# COBConnector.net
KiCad netlist of a schematic drawn in Altium Designer
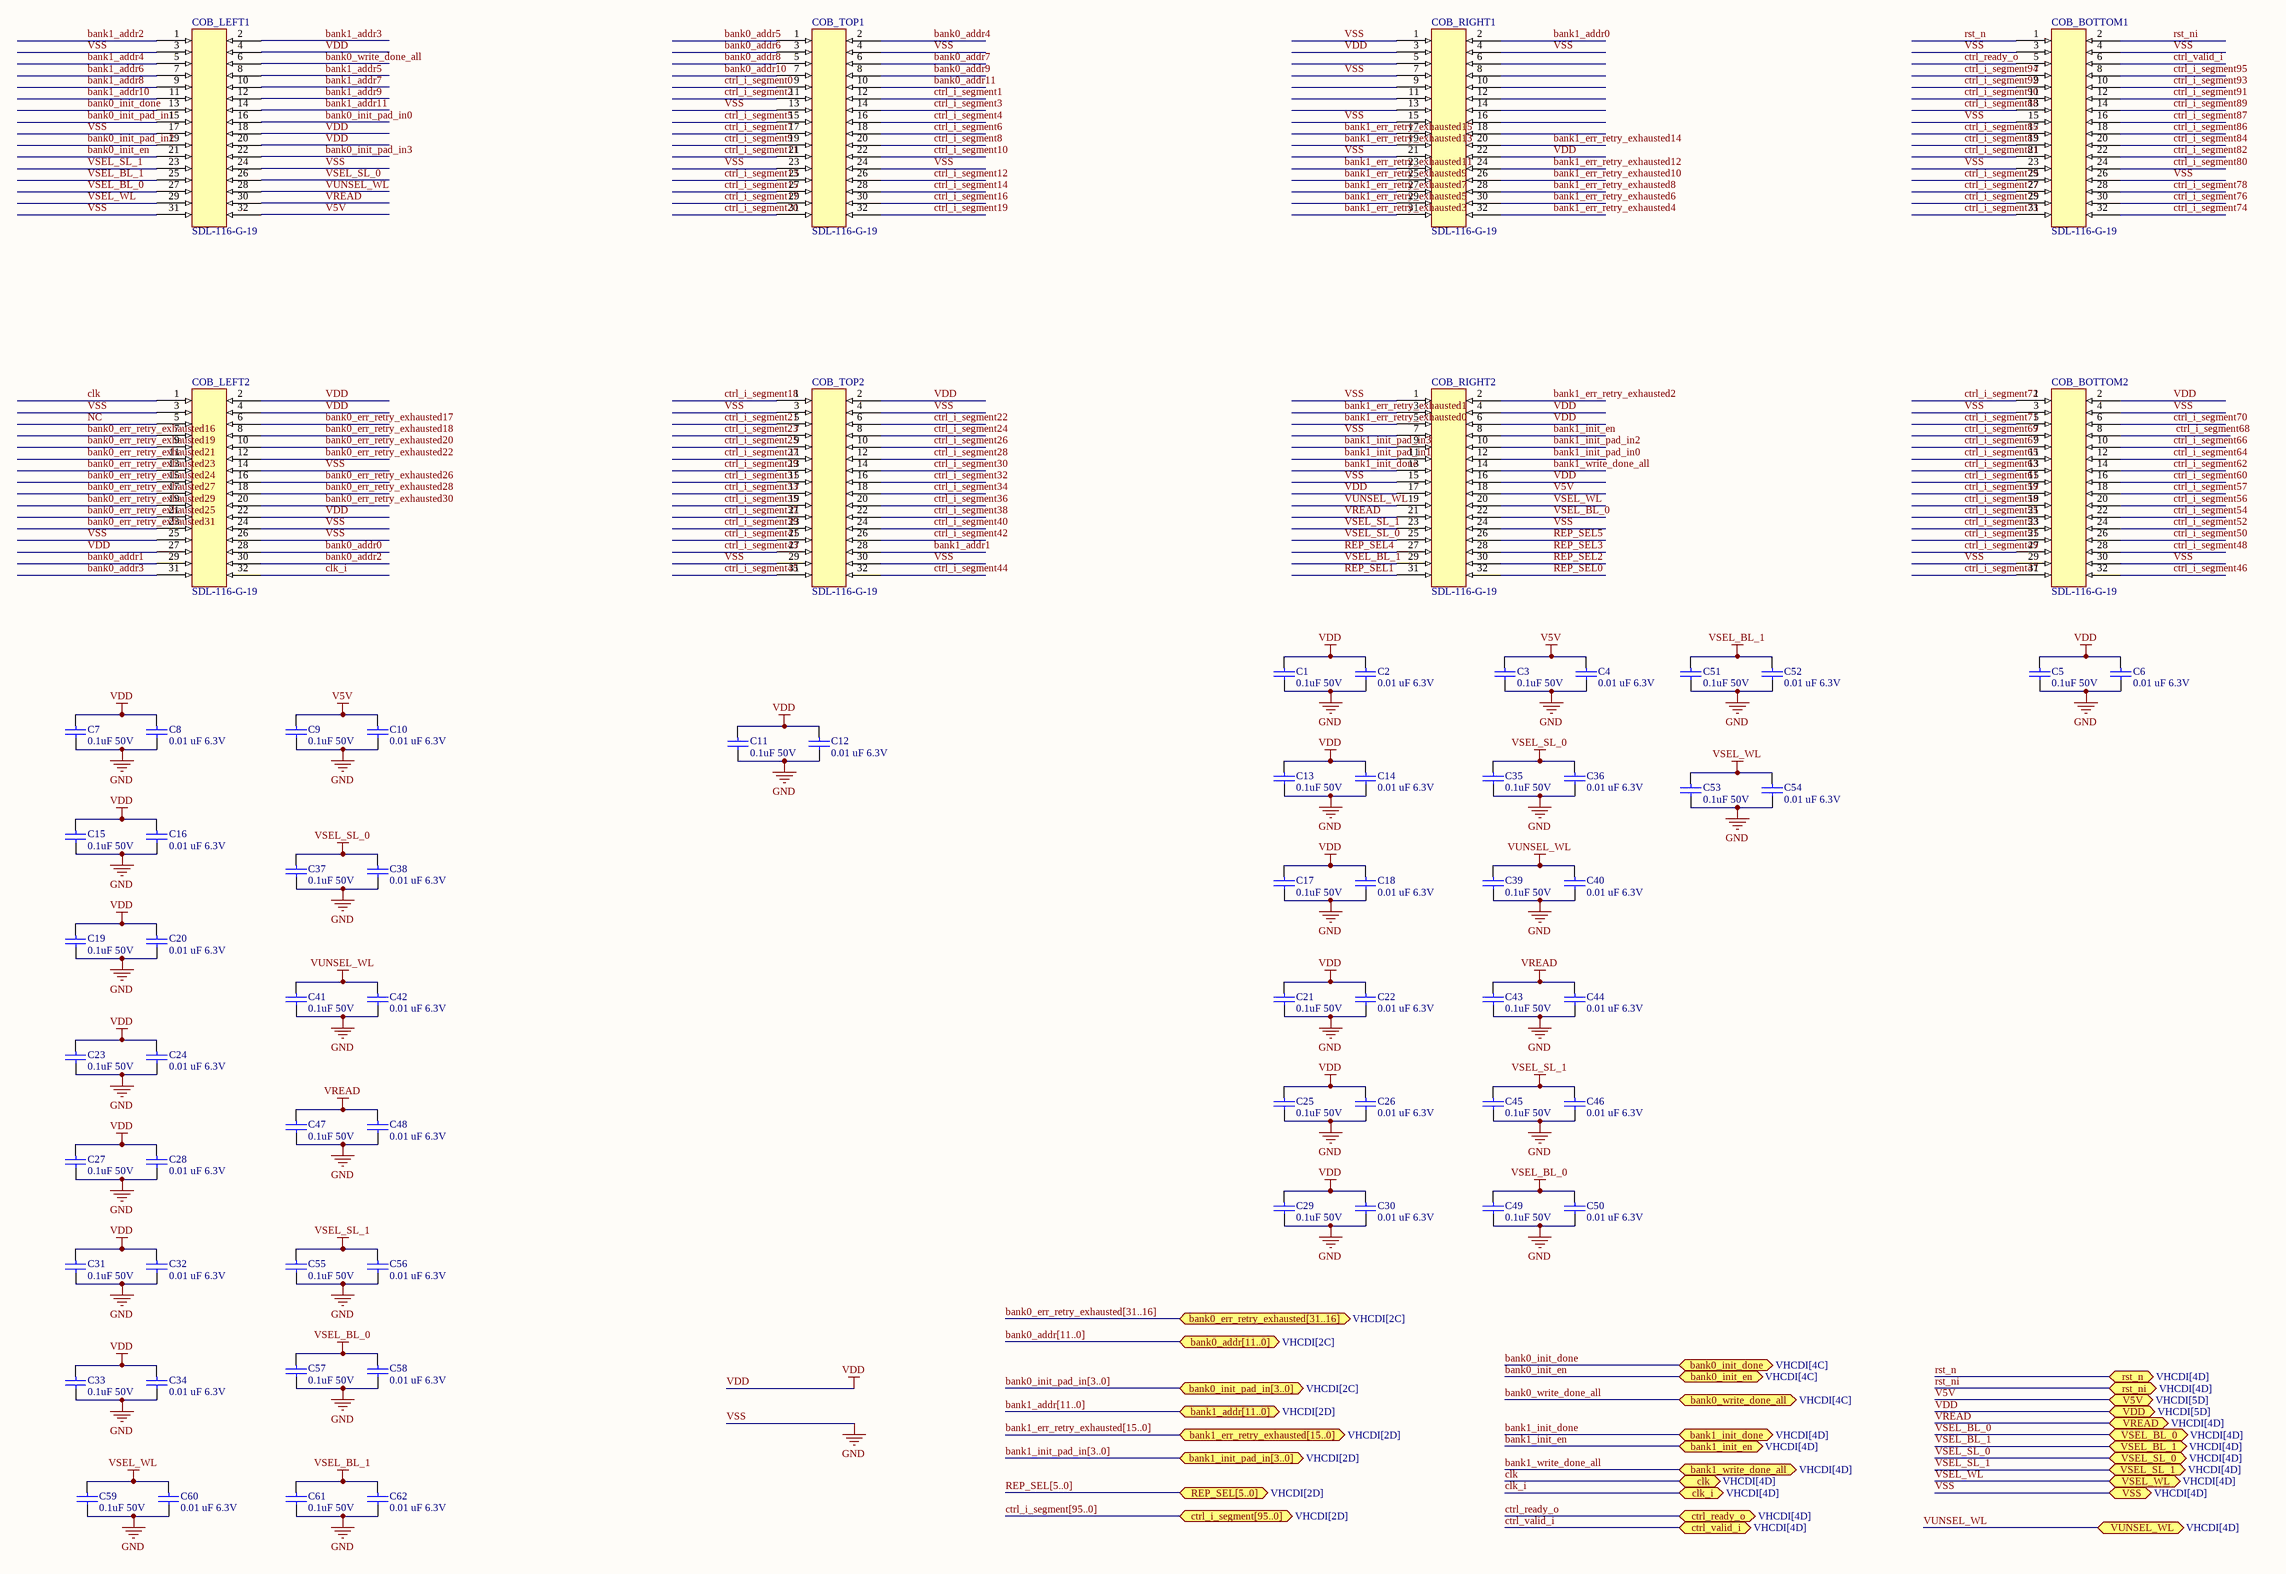
[diagram p0: COBConnector.SchDoc]

(export (version "E")
  (design (tool "Eeschema 10.0.6"))
  (components
    (comp (ref "C1")
      (value "0.1uF 50V")
      (footprint "C0603-XXXXXX-XXX")
      (description "0.1 µF ±20% 50V Ceramic Capacitor X7R 0603")
      (libsource (lib "00-100001-001") (part "C0603C104M5RAC7867"))
    )
    (comp (ref "C2")
      (value "0.01 uF 6.3V")
      (footprint "C0603-XXXXXX-XXX")
      (description "Multilayer Ceramic Capacitors MLCC - SMD/SMT 6.3V 0.01uF X7R 0603 20%")
      (libsource (lib "00-100001-001") (part "C0603F103M9RACTU"))
    )
    (comp (ref "C3")
      (value "0.1uF 50V")
      (footprint "C0603-XXXXXX-XXX")
      (description "0.1 µF ±20% 50V Ceramic Capacitor X7R 0603")
      (libsource (lib "00-100001-001") (part "C0603C104M5RAC7867"))
    )
    (comp (ref "C4")
      (value "0.01 uF 6.3V")
      (footprint "C0603-XXXXXX-XXX")
      (description "Multilayer Ceramic Capacitors MLCC - SMD/SMT 6.3V 0.01uF X7R 0603 20%")
      (libsource (lib "00-100001-001") (part "C0603F103M9RACTU"))
    )
    (comp (ref "C5")
      (value "0.1uF 50V")
      (footprint "C0603-XXXXXX-XXX")
      (description "0.1 µF ±20% 50V Ceramic Capacitor X7R 0603")
      (libsource (lib "00-100001-001") (part "C0603C104M5RAC7867"))
    )
    (comp (ref "C6")
      (value "0.01 uF 6.3V")
      (footprint "C0603-XXXXXX-XXX")
      (description "Multilayer Ceramic Capacitors MLCC - SMD/SMT 6.3V 0.01uF X7R 0603 20%")
      (libsource (lib "00-100001-001") (part "C0603F103M9RACTU"))
    )
    (comp (ref "C7")
      (value "0.1uF 50V")
      (footprint "C0603-XXXXXX-XXX")
      (description "0.1 µF ±20% 50V Ceramic Capacitor X7R 0603")
      (libsource (lib "00-100001-001") (part "C0603C104M5RAC7867"))
    )
    (comp (ref "C8")
      (value "0.01 uF 6.3V")
      (footprint "C0603-XXXXXX-XXX")
      (description "Multilayer Ceramic Capacitors MLCC - SMD/SMT 6.3V 0.01uF X7R 0603 20%")
      (libsource (lib "00-100001-001") (part "C0603F103M9RACTU"))
    )
    (comp (ref "C9")
      (value "0.1uF 50V")
      (footprint "C0603-XXXXXX-XXX")
      (description "0.1 µF ±20% 50V Ceramic Capacitor X7R 0603")
      (libsource (lib "00-100001-001") (part "C0603C104M5RAC7867"))
    )
    (comp (ref "C10")
      (value "0.01 uF 6.3V")
      (footprint "C0603-XXXXXX-XXX")
      (description "Multilayer Ceramic Capacitors MLCC - SMD/SMT 6.3V 0.01uF X7R 0603 20%")
      (libsource (lib "00-100001-001") (part "C0603F103M9RACTU"))
    )
    (comp (ref "C11")
      (value "0.1uF 50V")
      (footprint "C0603-XXXXXX-XXX")
      (description "0.1 µF ±20% 50V Ceramic Capacitor X7R 0603")
      (libsource (lib "00-100001-001") (part "C0603C104M5RAC7867"))
    )
    (comp (ref "C12")
      (value "0.01 uF 6.3V")
      (footprint "C0603-XXXXXX-XXX")
      (description "Multilayer Ceramic Capacitors MLCC - SMD/SMT 6.3V 0.01uF X7R 0603 20%")
      (libsource (lib "00-100001-001") (part "C0603F103M9RACTU"))
    )
    (comp (ref "C13")
      (value "0.1uF 50V")
      (footprint "C0603-XXXXXX-XXX")
      (description "0.1 µF ±20% 50V Ceramic Capacitor X7R 0603")
      (libsource (lib "00-100001-001") (part "C0603C104M5RAC7867"))
    )
    (comp (ref "C14")
      (value "0.01 uF 6.3V")
      (footprint "C0603-XXXXXX-XXX")
      (description "Multilayer Ceramic Capacitors MLCC - SMD/SMT 6.3V 0.01uF X7R 0603 20%")
      (libsource (lib "00-100001-001") (part "C0603F103M9RACTU"))
    )
    (comp (ref "C15")
      (value "0.1uF 50V")
      (footprint "C0603-XXXXXX-XXX")
      (description "0.1 µF ±20% 50V Ceramic Capacitor X7R 0603")
      (libsource (lib "00-100001-001") (part "C0603C104M5RAC7867"))
    )
    (comp (ref "C16")
      (value "0.01 uF 6.3V")
      (footprint "C0603-XXXXXX-XXX")
      (description "Multilayer Ceramic Capacitors MLCC - SMD/SMT 6.3V 0.01uF X7R 0603 20%")
      (libsource (lib "00-100001-001") (part "C0603F103M9RACTU"))
    )
    (comp (ref "C17")
      (value "0.1uF 50V")
      (footprint "C0603-XXXXXX-XXX")
      (description "0.1 µF ±20% 50V Ceramic Capacitor X7R 0603")
      (libsource (lib "00-100001-001") (part "C0603C104M5RAC7867"))
    )
    (comp (ref "C18")
      (value "0.01 uF 6.3V")
      (footprint "C0603-XXXXXX-XXX")
      (description "Multilayer Ceramic Capacitors MLCC - SMD/SMT 6.3V 0.01uF X7R 0603 20%")
      (libsource (lib "00-100001-001") (part "C0603F103M9RACTU"))
    )
    (comp (ref "C19")
      (value "0.1uF 50V")
      (footprint "C0603-XXXXXX-XXX")
      (description "0.1 µF ±20% 50V Ceramic Capacitor X7R 0603")
      (libsource (lib "00-100001-001") (part "C0603C104M5RAC7867"))
    )
    (comp (ref "C20")
      (value "0.01 uF 6.3V")
      (footprint "C0603-XXXXXX-XXX")
      (description "Multilayer Ceramic Capacitors MLCC - SMD/SMT 6.3V 0.01uF X7R 0603 20%")
      (libsource (lib "00-100001-001") (part "C0603F103M9RACTU"))
    )
    (comp (ref "C21")
      (value "0.1uF 50V")
      (footprint "C0603-XXXXXX-XXX")
      (description "0.1 µF ±20% 50V Ceramic Capacitor X7R 0603")
      (libsource (lib "00-100001-001") (part "C0603C104M5RAC7867"))
    )
    (comp (ref "C22")
      (value "0.01 uF 6.3V")
      (footprint "C0603-XXXXXX-XXX")
      (description "Multilayer Ceramic Capacitors MLCC - SMD/SMT 6.3V 0.01uF X7R 0603 20%")
      (libsource (lib "00-100001-001") (part "C0603F103M9RACTU"))
    )
    (comp (ref "C23")
      (value "0.1uF 50V")
      (footprint "C0603-XXXXXX-XXX")
      (description "0.1 µF ±20% 50V Ceramic Capacitor X7R 0603")
      (libsource (lib "00-100001-001") (part "C0603C104M5RAC7867"))
    )
    (comp (ref "C24")
      (value "0.01 uF 6.3V")
      (footprint "C0603-XXXXXX-XXX")
      (description "Multilayer Ceramic Capacitors MLCC - SMD/SMT 6.3V 0.01uF X7R 0603 20%")
      (libsource (lib "00-100001-001") (part "C0603F103M9RACTU"))
    )
    (comp (ref "C25")
      (value "0.1uF 50V")
      (footprint "C0603-XXXXXX-XXX")
      (description "0.1 µF ±20% 50V Ceramic Capacitor X7R 0603")
      (libsource (lib "00-100001-001") (part "C0603C104M5RAC7867"))
    )
    (comp (ref "C26")
      (value "0.01 uF 6.3V")
      (footprint "C0603-XXXXXX-XXX")
      (description "Multilayer Ceramic Capacitors MLCC - SMD/SMT 6.3V 0.01uF X7R 0603 20%")
      (libsource (lib "00-100001-001") (part "C0603F103M9RACTU"))
    )
    (comp (ref "C27")
      (value "0.1uF 50V")
      (footprint "C0603-XXXXXX-XXX")
      (description "0.1 µF ±20% 50V Ceramic Capacitor X7R 0603")
      (libsource (lib "00-100001-001") (part "C0603C104M5RAC7867"))
    )
    (comp (ref "C28")
      (value "0.01 uF 6.3V")
      (footprint "C0603-XXXXXX-XXX")
      (description "Multilayer Ceramic Capacitors MLCC - SMD/SMT 6.3V 0.01uF X7R 0603 20%")
      (libsource (lib "00-100001-001") (part "C0603F103M9RACTU"))
    )
    (comp (ref "C29")
      (value "0.1uF 50V")
      (footprint "C0603-XXXXXX-XXX")
      (description "0.1 µF ±20% 50V Ceramic Capacitor X7R 0603")
      (libsource (lib "00-100001-001") (part "C0603C104M5RAC7867"))
    )
    (comp (ref "C30")
      (value "0.01 uF 6.3V")
      (footprint "C0603-XXXXXX-XXX")
      (description "Multilayer Ceramic Capacitors MLCC - SMD/SMT 6.3V 0.01uF X7R 0603 20%")
      (libsource (lib "00-100001-001") (part "C0603F103M9RACTU"))
    )
    (comp (ref "C31")
      (value "0.1uF 50V")
      (footprint "C0603-XXXXXX-XXX")
      (description "0.1 µF ±20% 50V Ceramic Capacitor X7R 0603")
      (libsource (lib "00-100001-001") (part "C0603C104M5RAC7867"))
    )
    (comp (ref "C32")
      (value "0.01 uF 6.3V")
      (footprint "C0603-XXXXXX-XXX")
      (description "Multilayer Ceramic Capacitors MLCC - SMD/SMT 6.3V 0.01uF X7R 0603 20%")
      (libsource (lib "00-100001-001") (part "C0603F103M9RACTU"))
    )
    (comp (ref "C33")
      (value "0.1uF 50V")
      (footprint "C0603-XXXXXX-XXX")
      (description "0.1 µF ±20% 50V Ceramic Capacitor X7R 0603")
      (libsource (lib "00-100001-001") (part "C0603C104M5RAC7867"))
    )
    (comp (ref "C34")
      (value "0.01 uF 6.3V")
      (footprint "C0603-XXXXXX-XXX")
      (description "Multilayer Ceramic Capacitors MLCC - SMD/SMT 6.3V 0.01uF X7R 0603 20%")
      (libsource (lib "00-100001-001") (part "C0603F103M9RACTU"))
    )
    (comp (ref "C35")
      (value "0.1uF 50V")
      (footprint "C0603-XXXXXX-XXX")
      (description "0.1 µF ±20% 50V Ceramic Capacitor X7R 0603")
      (libsource (lib "00-100001-001") (part "C0603C104M5RAC7867"))
    )
    (comp (ref "C36")
      (value "0.01 uF 6.3V")
      (footprint "C0603-XXXXXX-XXX")
      (description "Multilayer Ceramic Capacitors MLCC - SMD/SMT 6.3V 0.01uF X7R 0603 20%")
      (libsource (lib "00-100001-001") (part "C0603F103M9RACTU"))
    )
    (comp (ref "C37")
      (value "0.1uF 50V")
      (footprint "C0603-XXXXXX-XXX")
      (description "0.1 µF ±20% 50V Ceramic Capacitor X7R 0603")
      (libsource (lib "00-100001-001") (part "C0603C104M5RAC7867"))
    )
    (comp (ref "C38")
      (value "0.01 uF 6.3V")
      (footprint "C0603-XXXXXX-XXX")
      (description "Multilayer Ceramic Capacitors MLCC - SMD/SMT 6.3V 0.01uF X7R 0603 20%")
      (libsource (lib "00-100001-001") (part "C0603F103M9RACTU"))
    )
    (comp (ref "C39")
      (value "0.1uF 50V")
      (footprint "C0603-XXXXXX-XXX")
      (description "0.1 µF ±20% 50V Ceramic Capacitor X7R 0603")
      (libsource (lib "00-100001-001") (part "C0603C104M5RAC7867"))
    )
    (comp (ref "C40")
      (value "0.01 uF 6.3V")
      (footprint "C0603-XXXXXX-XXX")
      (description "Multilayer Ceramic Capacitors MLCC - SMD/SMT 6.3V 0.01uF X7R 0603 20%")
      (libsource (lib "00-100001-001") (part "C0603F103M9RACTU"))
    )
    (comp (ref "C41")
      (value "0.1uF 50V")
      (footprint "C0603-XXXXXX-XXX")
      (description "0.1 µF ±20% 50V Ceramic Capacitor X7R 0603")
      (libsource (lib "00-100001-001") (part "C0603C104M5RAC7867"))
    )
    (comp (ref "C42")
      (value "0.01 uF 6.3V")
      (footprint "C0603-XXXXXX-XXX")
      (description "Multilayer Ceramic Capacitors MLCC - SMD/SMT 6.3V 0.01uF X7R 0603 20%")
      (libsource (lib "00-100001-001") (part "C0603F103M9RACTU"))
    )
    (comp (ref "C43")
      (value "0.1uF 50V")
      (footprint "C0603-XXXXXX-XXX")
      (description "0.1 µF ±20% 50V Ceramic Capacitor X7R 0603")
      (libsource (lib "00-100001-001") (part "C0603C104M5RAC7867"))
    )
    (comp (ref "C44")
      (value "0.01 uF 6.3V")
      (footprint "C0603-XXXXXX-XXX")
      (description "Multilayer Ceramic Capacitors MLCC - SMD/SMT 6.3V 0.01uF X7R 0603 20%")
      (libsource (lib "00-100001-001") (part "C0603F103M9RACTU"))
    )
    (comp (ref "C45")
      (value "0.1uF 50V")
      (footprint "C0603-XXXXXX-XXX")
      (description "0.1 µF ±20% 50V Ceramic Capacitor X7R 0603")
      (libsource (lib "00-100001-001") (part "C0603C104M5RAC7867"))
    )
    (comp (ref "C46")
      (value "0.01 uF 6.3V")
      (footprint "C0603-XXXXXX-XXX")
      (description "Multilayer Ceramic Capacitors MLCC - SMD/SMT 6.3V 0.01uF X7R 0603 20%")
      (libsource (lib "00-100001-001") (part "C0603F103M9RACTU"))
    )
    (comp (ref "C47")
      (value "0.1uF 50V")
      (footprint "C0603-XXXXXX-XXX")
      (description "0.1 µF ±20% 50V Ceramic Capacitor X7R 0603")
      (libsource (lib "00-100001-001") (part "C0603C104M5RAC7867"))
    )
    (comp (ref "C48")
      (value "0.01 uF 6.3V")
      (footprint "C0603-XXXXXX-XXX")
      (description "Multilayer Ceramic Capacitors MLCC - SMD/SMT 6.3V 0.01uF X7R 0603 20%")
      (libsource (lib "00-100001-001") (part "C0603F103M9RACTU"))
    )
    (comp (ref "C49")
      (value "0.1uF 50V")
      (footprint "C0603-XXXXXX-XXX")
      (description "0.1 µF ±20% 50V Ceramic Capacitor X7R 0603")
      (libsource (lib "00-100001-001") (part "C0603C104M5RAC7867"))
    )
    (comp (ref "C50")
      (value "0.01 uF 6.3V")
      (footprint "C0603-XXXXXX-XXX")
      (description "Multilayer Ceramic Capacitors MLCC - SMD/SMT 6.3V 0.01uF X7R 0603 20%")
      (libsource (lib "00-100001-001") (part "C0603F103M9RACTU"))
    )
    (comp (ref "C51")
      (value "0.1uF 50V")
      (footprint "C0603-XXXXXX-XXX")
      (description "0.1 µF ±20% 50V Ceramic Capacitor X7R 0603")
      (libsource (lib "00-100001-001") (part "C0603C104M5RAC7867"))
    )
    (comp (ref "C52")
      (value "0.01 uF 6.3V")
      (footprint "C0603-XXXXXX-XXX")
      (description "Multilayer Ceramic Capacitors MLCC - SMD/SMT 6.3V 0.01uF X7R 0603 20%")
      (libsource (lib "00-100001-001") (part "C0603F103M9RACTU"))
    )
    (comp (ref "C53")
      (value "0.1uF 50V")
      (footprint "C0603-XXXXXX-XXX")
      (description "0.1 µF ±20% 50V Ceramic Capacitor X7R 0603")
      (libsource (lib "00-100001-001") (part "C0603C104M5RAC7867"))
    )
    (comp (ref "C54")
      (value "0.01 uF 6.3V")
      (footprint "C0603-XXXXXX-XXX")
      (description "Multilayer Ceramic Capacitors MLCC - SMD/SMT 6.3V 0.01uF X7R 0603 20%")
      (libsource (lib "00-100001-001") (part "C0603F103M9RACTU"))
    )
    (comp (ref "C55")
      (value "0.1uF 50V")
      (footprint "C0603-XXXXXX-XXX")
      (description "0.1 µF ±20% 50V Ceramic Capacitor X7R 0603")
      (libsource (lib "00-100001-001") (part "C0603C104M5RAC7867"))
    )
    (comp (ref "C56")
      (value "0.01 uF 6.3V")
      (footprint "C0603-XXXXXX-XXX")
      (description "Multilayer Ceramic Capacitors MLCC - SMD/SMT 6.3V 0.01uF X7R 0603 20%")
      (libsource (lib "00-100001-001") (part "C0603F103M9RACTU"))
    )
    (comp (ref "C57")
      (value "0.1uF 50V")
      (footprint "C0603-XXXXXX-XXX")
      (description "0.1 µF ±20% 50V Ceramic Capacitor X7R 0603")
      (libsource (lib "00-100001-001") (part "C0603C104M5RAC7867"))
    )
    (comp (ref "C58")
      (value "0.01 uF 6.3V")
      (footprint "C0603-XXXXXX-XXX")
      (description "Multilayer Ceramic Capacitors MLCC - SMD/SMT 6.3V 0.01uF X7R 0603 20%")
      (libsource (lib "00-100001-001") (part "C0603F103M9RACTU"))
    )
    (comp (ref "C59")
      (value "0.1uF 50V")
      (footprint "C0603-XXXXXX-XXX")
      (description "0.1 µF ±20% 50V Ceramic Capacitor X7R 0603")
      (libsource (lib "00-100001-001") (part "C0603C104M5RAC7867"))
    )
    (comp (ref "C60")
      (value "0.01 uF 6.3V")
      (footprint "C0603-XXXXXX-XXX")
      (description "Multilayer Ceramic Capacitors MLCC - SMD/SMT 6.3V 0.01uF X7R 0603 20%")
      (libsource (lib "00-100001-001") (part "C0603F103M9RACTU"))
    )
    (comp (ref "C61")
      (value "0.1uF 50V")
      (footprint "C0603-XXXXXX-XXX")
      (description "0.1 µF ±20% 50V Ceramic Capacitor X7R 0603")
      (libsource (lib "00-100001-001") (part "C0603C104M5RAC7867"))
    )
    (comp (ref "C62")
      (value "0.01 uF 6.3V")
      (footprint "C0603-XXXXXX-XXX")
      (description "Multilayer Ceramic Capacitors MLCC - SMD/SMT 6.3V 0.01uF X7R 0603 20%")
      (libsource (lib "00-100001-001") (part "C0603F103M9RACTU"))
    )
    (comp (ref "COB_BOTTOM1")
      (value "SDL-116-G-19")
      (footprint "CON32_2X16_TU_DSL_SAI")
      (libsource (lib "00-100001-001") (part "SDL-116-G-19"))
    )
    (comp (ref "COB_BOTTOM2")
      (value "SDL-116-G-19")
      (footprint "CON32_2X16_TU_DSL_SAI")
      (libsource (lib "00-100001-001") (part "SDL-116-G-19"))
    )
    (comp (ref "COB_LEFT1")
      (value "SDL-116-G-19")
      (footprint "CON32_2X16_TU_DSL_SAI")
      (libsource (lib "00-100001-001") (part "SDL-116-G-19"))
    )
    (comp (ref "COB_LEFT2")
      (value "SDL-116-G-19")
      (footprint "CON32_2X16_TU_DSL_SAI")
      (libsource (lib "00-100001-001") (part "SDL-116-G-19"))
    )
    (comp (ref "COB_RIGHT1")
      (value "SDL-116-G-19")
      (footprint "CON32_2X16_TU_DSL_SAI")
      (libsource (lib "00-100001-001") (part "SDL-116-G-19"))
    )
    (comp (ref "COB_RIGHT2")
      (value "SDL-116-G-19")
      (footprint "CON32_2X16_TU_DSL_SAI")
      (libsource (lib "00-100001-001") (part "SDL-116-G-19"))
    )
    (comp (ref "COB_TOP1")
      (value "SDL-116-G-19")
      (footprint "CON32_2X16_TU_DSL_SAI")
      (libsource (lib "00-100001-001") (part "SDL-116-G-19"))
    )
    (comp (ref "COB_TOP2")
      (value "SDL-116-G-19")
      (footprint "CON32_2X16_TU_DSL_SAI")
      (libsource (lib "00-100001-001") (part "SDL-116-G-19"))
    )
  )
  (nets
    (net (code "1") (name "/NC") (class "Default") (node (ref "COB_LEFT2") (pin "5") (pintype "input")))
    (net (code "2") (name "/REP_SEL0") (class "Default")
      (node (ref "COB_RIGHT2") (pin "32") (pintype "input"))
    )
    (net (code "3") (name "/REP_SEL1") (class "Default")
      (node (ref "COB_RIGHT2") (pin "31") (pintype "input"))
    )
    (net (code "4") (name "/REP_SEL2") (class "Default")
      (node (ref "COB_RIGHT2") (pin "30") (pintype "input"))
    )
    (net (code "5") (name "/REP_SEL3") (class "Default")
      (node (ref "COB_RIGHT2") (pin "28") (pintype "input"))
    )
    (net (code "6") (name "/REP_SEL4") (class "Default")
      (node (ref "COB_RIGHT2") (pin "27") (pintype "input"))
    )
    (net (code "7") (name "/REP_SEL5") (class "Default")
      (node (ref "COB_RIGHT2") (pin "26") (pintype "input"))
    )
    (net (code "9") (name "/bank0_addr0") (class "Default")
      (node (ref "COB_LEFT2") (pin "28") (pintype "input"))
    )
    (net (code "10") (name "/bank0_addr1") (class "Default")
      (node (ref "COB_LEFT2") (pin "29") (pintype "input"))
    )
    (net (code "11") (name "/bank0_addr2") (class "Default")
      (node (ref "COB_LEFT2") (pin "30") (pintype "input"))
    )
    (net (code "12") (name "/bank0_addr3") (class "Default")
      (node (ref "COB_LEFT2") (pin "31") (pintype "input"))
    )
    (net (code "13") (name "/bank0_addr4") (class "Default")
      (node (ref "COB_TOP1") (pin "2") (pintype "input"))
    )
    (net (code "14") (name "/bank0_addr5") (class "Default")
      (node (ref "COB_TOP1") (pin "1") (pintype "input"))
    )
    (net (code "15") (name "/bank0_addr6") (class "Default")
      (node (ref "COB_TOP1") (pin "3") (pintype "input"))
    )
    (net (code "16") (name "/bank0_addr7") (class "Default")
      (node (ref "COB_TOP1") (pin "6") (pintype "input"))
    )
    (net (code "17") (name "/bank0_addr8") (class "Default")
      (node (ref "COB_TOP1") (pin "5") (pintype "input"))
    )
    (net (code "18") (name "/bank0_addr9") (class "Default")
      (node (ref "COB_TOP1") (pin "8") (pintype "input"))
    )
    (net (code "19") (name "/bank0_addr10") (class "Default")
      (node (ref "COB_TOP1") (pin "7") (pintype "input"))
    )
    (net (code "20") (name "/bank0_addr11") (class "Default")
      (node (ref "COB_TOP1") (pin "10") (pintype "input"))
    )
    (net (code "22") (name "/bank0_err_retry_exhausted16") (class "Default")
      (node (ref "COB_LEFT2") (pin "7") (pintype "input"))
    )
    (net (code "23") (name "/bank0_err_retry_exhausted17") (class "Default")
      (node (ref "COB_LEFT2") (pin "6") (pintype "input"))
    )
    (net (code "24") (name "/bank0_err_retry_exhausted18") (class "Default")
      (node (ref "COB_LEFT2") (pin "8") (pintype "input"))
    )
    (net (code "25") (name "/bank0_err_retry_exhausted19") (class "Default")
      (node (ref "COB_LEFT2") (pin "9") (pintype "input"))
    )
    (net (code "26") (name "/bank0_err_retry_exhausted20") (class "Default")
      (node (ref "COB_LEFT2") (pin "10") (pintype "input"))
    )
    (net (code "27") (name "/bank0_err_retry_exhausted21") (class "Default")
      (node (ref "COB_LEFT2") (pin "11") (pintype "input"))
    )
    (net (code "28") (name "/bank0_err_retry_exhausted22") (class "Default")
      (node (ref "COB_LEFT2") (pin "12") (pintype "input"))
    )
    (net (code "29") (name "/bank0_err_retry_exhausted23") (class "Default")
      (node (ref "COB_LEFT2") (pin "13") (pintype "input"))
    )
    (net (code "30") (name "/bank0_err_retry_exhausted24") (class "Default")
      (node (ref "COB_LEFT2") (pin "15") (pintype "input"))
    )
    (net (code "31") (name "/bank0_err_retry_exhausted25") (class "Default")
      (node (ref "COB_LEFT2") (pin "21") (pintype "input"))
    )
    (net (code "32") (name "/bank0_err_retry_exhausted26") (class "Default")
      (node (ref "COB_LEFT2") (pin "16") (pintype "input"))
    )
    (net (code "33") (name "/bank0_err_retry_exhausted27") (class "Default")
      (node (ref "COB_LEFT2") (pin "17") (pintype "input"))
    )
    (net (code "34") (name "/bank0_err_retry_exhausted28") (class "Default")
      (node (ref "COB_LEFT2") (pin "18") (pintype "input"))
    )
    (net (code "35") (name "/bank0_err_retry_exhausted29") (class "Default")
      (node (ref "COB_LEFT2") (pin "19") (pintype "input"))
    )
    (net (code "36") (name "/bank0_err_retry_exhausted30") (class "Default")
      (node (ref "COB_LEFT2") (pin "20") (pintype "input"))
    )
    (net (code "37") (name "/bank0_err_retry_exhausted31") (class "Default")
      (node (ref "COB_LEFT2") (pin "23") (pintype "input"))
    )
    (net (code "39") (name "/bank0_init_done") (class "Default")
      (node (ref "COB_LEFT1") (pin "13") (pintype "input"))
    )
    (net (code "40") (name "/bank0_init_en") (class "Default")
      (node (ref "COB_LEFT1") (pin "21") (pintype "input"))
    )
    (net (code "41") (name "/bank0_init_pad_in0") (class "Default")
      (node (ref "COB_LEFT1") (pin "16") (pintype "input"))
    )
    (net (code "42") (name "/bank0_init_pad_in1") (class "Default")
      (node (ref "COB_LEFT1") (pin "15") (pintype "input"))
    )
    (net (code "43") (name "/bank0_init_pad_in2") (class "Default")
      (node (ref "COB_LEFT1") (pin "19") (pintype "input"))
    )
    (net (code "44") (name "/bank0_init_pad_in3") (class "Default")
      (node (ref "COB_LEFT1") (pin "22") (pintype "input"))
    )
    (net (code "46") (name "/bank0_write_done_all") (class "Default")
      (node (ref "COB_LEFT1") (pin "6") (pintype "input"))
    )
    (net (code "47") (name "/bank1_addr0") (class "Default")
      (node (ref "COB_RIGHT1") (pin "2") (pintype "input"))
    )
    (net (code "48") (name "/bank1_addr1") (class "Default")
      (node (ref "COB_TOP2") (pin "28") (pintype "input"))
    )
    (net (code "49") (name "/bank1_addr2") (class "Default")
      (node (ref "COB_LEFT1") (pin "1") (pintype "input"))
    )
    (net (code "50") (name "/bank1_addr3") (class "Default")
      (node (ref "COB_LEFT1") (pin "2") (pintype "input"))
    )
    (net (code "51") (name "/bank1_addr4") (class "Default")
      (node (ref "COB_LEFT1") (pin "5") (pintype "input"))
    )
    (net (code "52") (name "/bank1_addr5") (class "Default")
      (node (ref "COB_LEFT1") (pin "8") (pintype "input"))
    )
    (net (code "53") (name "/bank1_addr6") (class "Default")
      (node (ref "COB_LEFT1") (pin "7") (pintype "input"))
    )
    (net (code "54") (name "/bank1_addr7") (class "Default")
      (node (ref "COB_LEFT1") (pin "10") (pintype "input"))
    )
    (net (code "55") (name "/bank1_addr8") (class "Default")
      (node (ref "COB_LEFT1") (pin "9") (pintype "input"))
    )
    (net (code "56") (name "/bank1_addr9") (class "Default")
      (node (ref "COB_LEFT1") (pin "12") (pintype "input"))
    )
    (net (code "57") (name "/bank1_addr10") (class "Default")
      (node (ref "COB_LEFT1") (pin "11") (pintype "input"))
    )
    (net (code "58") (name "/bank1_addr11") (class "Default")
      (node (ref "COB_LEFT1") (pin "14") (pintype "input"))
    )
    (net (code "60") (name "/bank1_err_retry_exhausted0") (class "Default")
      (node (ref "COB_RIGHT2") (pin "5") (pintype "input"))
    )
    (net (code "61") (name "/bank1_err_retry_exhausted1") (class "Default")
      (node (ref "COB_RIGHT2") (pin "3") (pintype "input"))
    )
    (net (code "62") (name "/bank1_err_retry_exhausted2") (class "Default")
      (node (ref "COB_RIGHT2") (pin "2") (pintype "input"))
    )
    (net (code "63") (name "/bank1_err_retry_exhausted3") (class "Default")
      (node (ref "COB_RIGHT1") (pin "31") (pintype "input"))
    )
    (net (code "64") (name "/bank1_err_retry_exhausted4") (class "Default")
      (node (ref "COB_RIGHT1") (pin "32") (pintype "input"))
    )
    (net (code "65") (name "/bank1_err_retry_exhausted5") (class "Default")
      (node (ref "COB_RIGHT1") (pin "29") (pintype "input"))
    )
    (net (code "66") (name "/bank1_err_retry_exhausted6") (class "Default")
      (node (ref "COB_RIGHT1") (pin "30") (pintype "input"))
    )
    (net (code "67") (name "/bank1_err_retry_exhausted7") (class "Default")
      (node (ref "COB_RIGHT1") (pin "27") (pintype "input"))
    )
    (net (code "68") (name "/bank1_err_retry_exhausted8") (class "Default")
      (node (ref "COB_RIGHT1") (pin "28") (pintype "input"))
    )
    (net (code "69") (name "/bank1_err_retry_exhausted9") (class "Default")
      (node (ref "COB_RIGHT1") (pin "25") (pintype "input"))
    )
    (net (code "70") (name "/bank1_err_retry_exhausted10") (class "Default")
      (node (ref "COB_RIGHT1") (pin "26") (pintype "input"))
    )
    (net (code "71") (name "/bank1_err_retry_exhausted11") (class "Default")
      (node (ref "COB_RIGHT1") (pin "23") (pintype "input"))
    )
    (net (code "72") (name "/bank1_err_retry_exhausted12") (class "Default")
      (node (ref "COB_RIGHT1") (pin "24") (pintype "input"))
    )
    (net (code "73") (name "/bank1_err_retry_exhausted13") (class "Default")
      (node (ref "COB_RIGHT1") (pin "19") (pintype "input"))
    )
    (net (code "74") (name "/bank1_err_retry_exhausted14") (class "Default")
      (node (ref "COB_RIGHT1") (pin "20") (pintype "input"))
    )
    (net (code "75") (name "/bank1_err_retry_exhausted15") (class "Default")
      (node (ref "COB_RIGHT1") (pin "17") (pintype "input"))
    )
    (net (code "77") (name "/bank1_init_done") (class "Default")
      (node (ref "COB_RIGHT2") (pin "13") (pintype "input"))
    )
    (net (code "78") (name "/bank1_init_en") (class "Default")
      (node (ref "COB_RIGHT2") (pin "8") (pintype "input"))
    )
    (net (code "79") (name "/bank1_init_pad_in0") (class "Default")
      (node (ref "COB_RIGHT2") (pin "12") (pintype "input"))
    )
    (net (code "80") (name "/bank1_init_pad_in1") (class "Default")
      (node (ref "COB_RIGHT2") (pin "11") (pintype "input"))
    )
    (net (code "81") (name "/bank1_init_pad_in2") (class "Default")
      (node (ref "COB_RIGHT2") (pin "10") (pintype "input"))
    )
    (net (code "82") (name "/bank1_init_pad_in3") (class "Default")
      (node (ref "COB_RIGHT2") (pin "9") (pintype "input"))
    )
    (net (code "84") (name "/bank1_write_done_all") (class "Default")
      (node (ref "COB_RIGHT2") (pin "14") (pintype "input"))
    )
    (net (code "85") (name "/clk") (class "Default") (node (ref "COB_LEFT2") (pin "1") (pintype "input")))
    (net (code "86") (name "/clk_i") (class "Default") (node (ref "COB_LEFT2") (pin "32") (pintype "input")))
    (net (code "87") (name "/ctrl_i_segment0") (class "Default")
      (node (ref "COB_TOP1") (pin "9") (pintype "input"))
    )
    (net (code "88") (name "/ctrl_i_segment1") (class "Default")
      (node (ref "COB_TOP1") (pin "12") (pintype "input"))
    )
    (net (code "89") (name "/ctrl_i_segment2") (class "Default")
      (node (ref "COB_TOP1") (pin "11") (pintype "input"))
    )
    (net (code "90") (name "/ctrl_i_segment3") (class "Default")
      (node (ref "COB_TOP1") (pin "14") (pintype "input"))
    )
    (net (code "91") (name "/ctrl_i_segment4") (class "Default")
      (node (ref "COB_TOP1") (pin "16") (pintype "input"))
    )
    (net (code "92") (name "/ctrl_i_segment5") (class "Default")
      (node (ref "COB_TOP1") (pin "15") (pintype "input"))
    )
    (net (code "93") (name "/ctrl_i_segment6") (class "Default")
      (node (ref "COB_TOP1") (pin "18") (pintype "input"))
    )
    (net (code "94") (name "/ctrl_i_segment7") (class "Default")
      (node (ref "COB_TOP1") (pin "17") (pintype "input"))
    )
    (net (code "95") (name "/ctrl_i_segment8") (class "Default")
      (node (ref "COB_TOP1") (pin "20") (pintype "input"))
    )
    (net (code "96") (name "/ctrl_i_segment9") (class "Default")
      (node (ref "COB_TOP1") (pin "19") (pintype "input"))
    )
    (net (code "97") (name "/ctrl_i_segment10") (class "Default")
      (node (ref "COB_TOP1") (pin "22") (pintype "input"))
    )
    (net (code "98") (name "/ctrl_i_segment11") (class "Default")
      (node (ref "COB_TOP1") (pin "21") (pintype "input"))
    )
    (net (code "99") (name "/ctrl_i_segment12") (class "Default")
      (node (ref "COB_TOP1") (pin "26") (pintype "input"))
    )
    (net (code "100") (name "/ctrl_i_segment13") (class "Default")
      (node (ref "COB_TOP1") (pin "25") (pintype "input"))
    )
    (net (code "101") (name "/ctrl_i_segment14") (class "Default")
      (node (ref "COB_TOP1") (pin "28") (pintype "input"))
    )
    (net (code "102") (name "/ctrl_i_segment15") (class "Default")
      (node (ref "COB_TOP1") (pin "27") (pintype "input"))
    )
    (net (code "103") (name "/ctrl_i_segment16") (class "Default")
      (node (ref "COB_TOP1") (pin "30") (pintype "input"))
    )
    (net (code "104") (name "/ctrl_i_segment17") (class "Default")
      (node (ref "COB_TOP1") (pin "29") (pintype "input"))
    )
    (net (code "105") (name "/ctrl_i_segment18") (class "Default")
      (node (ref "COB_TOP2") (pin "1") (pintype "input"))
    )
    (net (code "106") (name "/ctrl_i_segment19") (class "Default")
      (node (ref "COB_TOP1") (pin "32") (pintype "input"))
    )
    (net (code "107") (name "/ctrl_i_segment20") (class "Default")
      (node (ref "COB_TOP1") (pin "31") (pintype "input"))
    )
    (net (code "108") (name "/ctrl_i_segment21") (class "Default")
      (node (ref "COB_TOP2") (pin "5") (pintype "input"))
    )
    (net (code "109") (name "/ctrl_i_segment22") (class "Default")
      (node (ref "COB_TOP2") (pin "6") (pintype "input"))
    )
    (net (code "110") (name "/ctrl_i_segment23") (class "Default")
      (node (ref "COB_TOP2") (pin "7") (pintype "input"))
    )
    (net (code "111") (name "/ctrl_i_segment24") (class "Default")
      (node (ref "COB_TOP2") (pin "8") (pintype "input"))
    )
    (net (code "112") (name "/ctrl_i_segment25") (class "Default")
      (node (ref "COB_TOP2") (pin "9") (pintype "input"))
    )
    (net (code "113") (name "/ctrl_i_segment26") (class "Default")
      (node (ref "COB_TOP2") (pin "10") (pintype "input"))
    )
    (net (code "114") (name "/ctrl_i_segment27") (class "Default")
      (node (ref "COB_TOP2") (pin "11") (pintype "input"))
    )
    (net (code "115") (name "/ctrl_i_segment28") (class "Default")
      (node (ref "COB_TOP2") (pin "12") (pintype "input"))
    )
    (net (code "116") (name "/ctrl_i_segment29") (class "Default")
      (node (ref "COB_TOP2") (pin "13") (pintype "input"))
    )
    (net (code "117") (name "/ctrl_i_segment30") (class "Default")
      (node (ref "COB_TOP2") (pin "14") (pintype "input"))
    )
    (net (code "118") (name "/ctrl_i_segment31") (class "Default")
      (node (ref "COB_TOP2") (pin "15") (pintype "input"))
    )
    (net (code "119") (name "/ctrl_i_segment32") (class "Default")
      (node (ref "COB_TOP2") (pin "16") (pintype "input"))
    )
    (net (code "120") (name "/ctrl_i_segment33") (class "Default")
      (node (ref "COB_TOP2") (pin "17") (pintype "input"))
    )
    (net (code "121") (name "/ctrl_i_segment34") (class "Default")
      (node (ref "COB_TOP2") (pin "18") (pintype "input"))
    )
    (net (code "122") (name "/ctrl_i_segment35") (class "Default")
      (node (ref "COB_TOP2") (pin "19") (pintype "input"))
    )
    (net (code "123") (name "/ctrl_i_segment36") (class "Default")
      (node (ref "COB_TOP2") (pin "20") (pintype "input"))
    )
    (net (code "124") (name "/ctrl_i_segment37") (class "Default")
      (node (ref "COB_TOP2") (pin "21") (pintype "input"))
    )
    (net (code "125") (name "/ctrl_i_segment38") (class "Default")
      (node (ref "COB_TOP2") (pin "22") (pintype "input"))
    )
    (net (code "126") (name "/ctrl_i_segment39") (class "Default")
      (node (ref "COB_TOP2") (pin "23") (pintype "input"))
    )
    (net (code "127") (name "/ctrl_i_segment40") (class "Default")
      (node (ref "COB_TOP2") (pin "24") (pintype "input"))
    )
    (net (code "128") (name "/ctrl_i_segment41") (class "Default")
      (node (ref "COB_TOP2") (pin "25") (pintype "input"))
    )
    (net (code "129") (name "/ctrl_i_segment42") (class "Default")
      (node (ref "COB_TOP2") (pin "26") (pintype "input"))
    )
    (net (code "130") (name "/ctrl_i_segment43") (class "Default")
      (node (ref "COB_TOP2") (pin "27") (pintype "input"))
    )
    (net (code "131") (name "/ctrl_i_segment44") (class "Default")
      (node (ref "COB_TOP2") (pin "32") (pintype "input"))
    )
    (net (code "132") (name "/ctrl_i_segment45") (class "Default")
      (node (ref "COB_TOP2") (pin "31") (pintype "input"))
    )
    (net (code "133") (name "/ctrl_i_segment46") (class "Default")
      (node (ref "COB_BOTTOM2") (pin "32") (pintype "input"))
    )
    (net (code "134") (name "/ctrl_i_segment47") (class "Default")
      (node (ref "COB_BOTTOM2") (pin "31") (pintype "input"))
    )
    (net (code "135") (name "/ctrl_i_segment48") (class "Default")
      (node (ref "COB_BOTTOM2") (pin "28") (pintype "input"))
    )
    (net (code "136") (name "/ctrl_i_segment49") (class "Default")
      (node (ref "COB_BOTTOM2") (pin "27") (pintype "input"))
    )
    (net (code "137") (name "/ctrl_i_segment50") (class "Default")
      (node (ref "COB_BOTTOM2") (pin "26") (pintype "input"))
    )
    (net (code "138") (name "/ctrl_i_segment51") (class "Default")
      (node (ref "COB_BOTTOM2") (pin "25") (pintype "input"))
    )
    (net (code "139") (name "/ctrl_i_segment52") (class "Default")
      (node (ref "COB_BOTTOM2") (pin "24") (pintype "input"))
    )
    (net (code "140") (name "/ctrl_i_segment53") (class "Default")
      (node (ref "COB_BOTTOM2") (pin "23") (pintype "input"))
    )
    (net (code "141") (name "/ctrl_i_segment54") (class "Default")
      (node (ref "COB_BOTTOM2") (pin "22") (pintype "input"))
    )
    (net (code "142") (name "/ctrl_i_segment55") (class "Default")
      (node (ref "COB_BOTTOM2") (pin "21") (pintype "input"))
    )
    (net (code "143") (name "/ctrl_i_segment56") (class "Default")
      (node (ref "COB_BOTTOM2") (pin "20") (pintype "input"))
    )
    (net (code "144") (name "/ctrl_i_segment57") (class "Default")
      (node (ref "COB_BOTTOM2") (pin "18") (pintype "input"))
    )
    (net (code "145") (name "/ctrl_i_segment58") (class "Default")
      (node (ref "COB_BOTTOM2") (pin "19") (pintype "input"))
    )
    (net (code "146") (name "/ctrl_i_segment59") (class "Default")
      (node (ref "COB_BOTTOM2") (pin "17") (pintype "input"))
    )
    (net (code "147") (name "/ctrl_i_segment60") (class "Default")
      (node (ref "COB_BOTTOM2") (pin "16") (pintype "input"))
    )
    (net (code "148") (name "/ctrl_i_segment61") (class "Default")
      (node (ref "COB_BOTTOM2") (pin "15") (pintype "input"))
    )
    (net (code "149") (name "/ctrl_i_segment62") (class "Default")
      (node (ref "COB_BOTTOM2") (pin "14") (pintype "input"))
    )
    (net (code "150") (name "/ctrl_i_segment63") (class "Default")
      (node (ref "COB_BOTTOM2") (pin "13") (pintype "input"))
    )
    (net (code "151") (name "/ctrl_i_segment64") (class "Default")
      (node (ref "COB_BOTTOM2") (pin "12") (pintype "input"))
    )
    (net (code "152") (name "/ctrl_i_segment65") (class "Default")
      (node (ref "COB_BOTTOM2") (pin "11") (pintype "input"))
    )
    (net (code "153") (name "/ctrl_i_segment66") (class "Default")
      (node (ref "COB_BOTTOM2") (pin "10") (pintype "input"))
    )
    (net (code "154") (name "/ctrl_i_segment67") (class "Default")
      (node (ref "COB_BOTTOM2") (pin "9") (pintype "input"))
    )
    (net (code "155") (name "/ctrl_i_segment68") (class "Default")
      (node (ref "COB_BOTTOM2") (pin "8") (pintype "input"))
    )
    (net (code "156") (name "/ctrl_i_segment69") (class "Default")
      (node (ref "COB_BOTTOM2") (pin "7") (pintype "input"))
    )
    (net (code "157") (name "/ctrl_i_segment70") (class "Default")
      (node (ref "COB_BOTTOM2") (pin "6") (pintype "input"))
    )
    (net (code "158") (name "/ctrl_i_segment71") (class "Default")
      (node (ref "COB_BOTTOM2") (pin "5") (pintype "input"))
    )
    (net (code "159") (name "/ctrl_i_segment72") (class "Default")
      (node (ref "COB_BOTTOM2") (pin "1") (pintype "input"))
    )
    (net (code "160") (name "/ctrl_i_segment73") (class "Default")
      (node (ref "COB_BOTTOM1") (pin "31") (pintype "input"))
    )
    (net (code "161") (name "/ctrl_i_segment74") (class "Default")
      (node (ref "COB_BOTTOM1") (pin "32") (pintype "input"))
    )
    (net (code "162") (name "/ctrl_i_segment75") (class "Default")
      (node (ref "COB_BOTTOM1") (pin "29") (pintype "input"))
    )
    (net (code "163") (name "/ctrl_i_segment76") (class "Default")
      (node (ref "COB_BOTTOM1") (pin "30") (pintype "input"))
    )
    (net (code "164") (name "/ctrl_i_segment77") (class "Default")
      (node (ref "COB_BOTTOM1") (pin "27") (pintype "input"))
    )
    (net (code "165") (name "/ctrl_i_segment78") (class "Default")
      (node (ref "COB_BOTTOM1") (pin "28") (pintype "input"))
    )
    (net (code "166") (name "/ctrl_i_segment79") (class "Default")
      (node (ref "COB_BOTTOM1") (pin "25") (pintype "input"))
    )
    (net (code "167") (name "/ctrl_i_segment80") (class "Default")
      (node (ref "COB_BOTTOM1") (pin "24") (pintype "input"))
    )
    (net (code "168") (name "/ctrl_i_segment81") (class "Default")
      (node (ref "COB_BOTTOM1") (pin "21") (pintype "input"))
    )
    (net (code "169") (name "/ctrl_i_segment82") (class "Default")
      (node (ref "COB_BOTTOM1") (pin "22") (pintype "input"))
    )
    (net (code "170") (name "/ctrl_i_segment83") (class "Default")
      (node (ref "COB_BOTTOM1") (pin "19") (pintype "input"))
    )
    (net (code "171") (name "/ctrl_i_segment84") (class "Default")
      (node (ref "COB_BOTTOM1") (pin "20") (pintype "input"))
    )
    (net (code "172") (name "/ctrl_i_segment85") (class "Default")
      (node (ref "COB_BOTTOM1") (pin "17") (pintype "input"))
    )
    (net (code "173") (name "/ctrl_i_segment86") (class "Default")
      (node (ref "COB_BOTTOM1") (pin "18") (pintype "input"))
    )
    (net (code "174") (name "/ctrl_i_segment87") (class "Default")
      (node (ref "COB_BOTTOM1") (pin "16") (pintype "input"))
    )
    (net (code "175") (name "/ctrl_i_segment88") (class "Default")
      (node (ref "COB_BOTTOM1") (pin "13") (pintype "input"))
    )
    (net (code "176") (name "/ctrl_i_segment89") (class "Default")
      (node (ref "COB_BOTTOM1") (pin "14") (pintype "input"))
    )
    (net (code "177") (name "/ctrl_i_segment90") (class "Default")
      (node (ref "COB_BOTTOM1") (pin "11") (pintype "input"))
    )
    (net (code "178") (name "/ctrl_i_segment91") (class "Default")
      (node (ref "COB_BOTTOM1") (pin "12") (pintype "input"))
    )
    (net (code "179") (name "/ctrl_i_segment92") (class "Default")
      (node (ref "COB_BOTTOM1") (pin "9") (pintype "input"))
    )
    (net (code "180") (name "/ctrl_i_segment93") (class "Default")
      (node (ref "COB_BOTTOM1") (pin "10") (pintype "input"))
    )
    (net (code "181") (name "/ctrl_i_segment94") (class "Default")
      (node (ref "COB_BOTTOM1") (pin "7") (pintype "input"))
    )
    (net (code "182") (name "/ctrl_i_segment95") (class "Default")
      (node (ref "COB_BOTTOM1") (pin "8") (pintype "input"))
    )
    (net (code "184") (name "/ctrl_ready_o") (class "Default")
      (node (ref "COB_BOTTOM1") (pin "5") (pintype "input"))
    )
    (net (code "185") (name "/ctrl_valid_i") (class "Default")
      (node (ref "COB_BOTTOM1") (pin "6") (pintype "input"))
    )
    (net (code "186") (name "/rst_n") (class "Default")
      (node (ref "COB_BOTTOM1") (pin "1") (pintype "input"))
    )
    (net (code "187") (name "/rst_ni") (class "Default")
      (node (ref "COB_BOTTOM1") (pin "2") (pintype "input"))
    )
    (net (code "188") (name "GND") (class "Default")
      (node (ref "C1") (pin "2") (pinfunction "2_2") (pintype "passive"))
      (node (ref "C10") (pin "2") (pinfunction "2_2") (pintype "passive"))
      (node (ref "C11") (pin "2") (pinfunction "2_2") (pintype "passive"))
      (node (ref "C12") (pin "2") (pinfunction "2_2") (pintype "passive"))
      (node (ref "C13") (pin "2") (pinfunction "2_2") (pintype "passive"))
      (node (ref "C14") (pin "2") (pinfunction "2_2") (pintype "passive"))
      (node (ref "C15") (pin "2") (pinfunction "2_2") (pintype "passive"))
      (node (ref "C16") (pin "2") (pinfunction "2_2") (pintype "passive"))
      (node (ref "C17") (pin "2") (pinfunction "2_2") (pintype "passive"))
      (node (ref "C18") (pin "2") (pinfunction "2_2") (pintype "passive"))
      (node (ref "C19") (pin "2") (pinfunction "2_2") (pintype "passive"))
      (node (ref "C2") (pin "2") (pinfunction "2_2") (pintype "passive"))
      (node (ref "C20") (pin "2") (pinfunction "2_2") (pintype "passive"))
      (node (ref "C21") (pin "2") (pinfunction "2_2") (pintype "passive"))
      (node (ref "C22") (pin "2") (pinfunction "2_2") (pintype "passive"))
      (node (ref "C23") (pin "2") (pinfunction "2_2") (pintype "passive"))
      (node (ref "C24") (pin "2") (pinfunction "2_2") (pintype "passive"))
      (node (ref "C25") (pin "2") (pinfunction "2_2") (pintype "passive"))
      (node (ref "C26") (pin "2") (pinfunction "2_2") (pintype "passive"))
      (node (ref "C27") (pin "2") (pinfunction "2_2") (pintype "passive"))
      (node (ref "C28") (pin "2") (pinfunction "2_2") (pintype "passive"))
      (node (ref "C29") (pin "2") (pinfunction "2_2") (pintype "passive"))
      (node (ref "C3") (pin "2") (pinfunction "2_2") (pintype "passive"))
      (node (ref "C30") (pin "2") (pinfunction "2_2") (pintype "passive"))
      (node (ref "C31") (pin "2") (pinfunction "2_2") (pintype "passive"))
      (node (ref "C32") (pin "2") (pinfunction "2_2") (pintype "passive"))
      (node (ref "C33") (pin "2") (pinfunction "2_2") (pintype "passive"))
      (node (ref "C34") (pin "2") (pinfunction "2_2") (pintype "passive"))
      (node (ref "C35") (pin "2") (pinfunction "2_2") (pintype "passive"))
      (node (ref "C36") (pin "2") (pinfunction "2_2") (pintype "passive"))
      (node (ref "C37") (pin "2") (pinfunction "2_2") (pintype "passive"))
      (node (ref "C38") (pin "2") (pinfunction "2_2") (pintype "passive"))
      (node (ref "C39") (pin "2") (pinfunction "2_2") (pintype "passive"))
      (node (ref "C4") (pin "2") (pinfunction "2_2") (pintype "passive"))
      (node (ref "C40") (pin "2") (pinfunction "2_2") (pintype "passive"))
      (node (ref "C41") (pin "2") (pinfunction "2_2") (pintype "passive"))
      (node (ref "C42") (pin "2") (pinfunction "2_2") (pintype "passive"))
      (node (ref "C43") (pin "2") (pinfunction "2_2") (pintype "passive"))
      (node (ref "C44") (pin "2") (pinfunction "2_2") (pintype "passive"))
      (node (ref "C45") (pin "2") (pinfunction "2_2") (pintype "passive"))
      (node (ref "C46") (pin "2") (pinfunction "2_2") (pintype "passive"))
      (node (ref "C47") (pin "2") (pinfunction "2_2") (pintype "passive"))
      (node (ref "C48") (pin "2") (pinfunction "2_2") (pintype "passive"))
      (node (ref "C49") (pin "2") (pinfunction "2_2") (pintype "passive"))
      (node (ref "C5") (pin "2") (pinfunction "2_2") (pintype "passive"))
      (node (ref "C50") (pin "2") (pinfunction "2_2") (pintype "passive"))
      (node (ref "C51") (pin "2") (pinfunction "2_2") (pintype "passive"))
      (node (ref "C52") (pin "2") (pinfunction "2_2") (pintype "passive"))
      (node (ref "C53") (pin "2") (pinfunction "2_2") (pintype "passive"))
      (node (ref "C54") (pin "2") (pinfunction "2_2") (pintype "passive"))
      (node (ref "C55") (pin "2") (pinfunction "2_2") (pintype "passive"))
      (node (ref "C56") (pin "2") (pinfunction "2_2") (pintype "passive"))
      (node (ref "C57") (pin "2") (pinfunction "2_2") (pintype "passive"))
      (node (ref "C58") (pin "2") (pinfunction "2_2") (pintype "passive"))
      (node (ref "C59") (pin "2") (pinfunction "2_2") (pintype "passive"))
      (node (ref "C6") (pin "2") (pinfunction "2_2") (pintype "passive"))
      (node (ref "C60") (pin "2") (pinfunction "2_2") (pintype "passive"))
      (node (ref "C61") (pin "2") (pinfunction "2_2") (pintype "passive"))
      (node (ref "C62") (pin "2") (pinfunction "2_2") (pintype "passive"))
      (node (ref "C7") (pin "2") (pinfunction "2_2") (pintype "passive"))
      (node (ref "C8") (pin "2") (pinfunction "2_2") (pintype "passive"))
      (node (ref "C9") (pin "2") (pinfunction "2_2") (pintype "passive"))
      (node (ref "COB_BOTTOM1") (pin "15") (pintype "input"))
      (node (ref "COB_BOTTOM1") (pin "23") (pintype "input"))
      (node (ref "COB_BOTTOM1") (pin "26") (pintype "input"))
      (node (ref "COB_BOTTOM1") (pin "3") (pintype "input"))
      (node (ref "COB_BOTTOM1") (pin "4") (pintype "input"))
      (node (ref "COB_BOTTOM2") (pin "29") (pintype "input"))
      (node (ref "COB_BOTTOM2") (pin "3") (pintype "input"))
      (node (ref "COB_BOTTOM2") (pin "30") (pintype "input"))
      (node (ref "COB_BOTTOM2") (pin "4") (pintype "input"))
      (node (ref "COB_LEFT1") (pin "17") (pintype "input"))
      (node (ref "COB_LEFT1") (pin "24") (pintype "input"))
      (node (ref "COB_LEFT1") (pin "3") (pintype "input"))
      (node (ref "COB_LEFT1") (pin "31") (pintype "input"))
      (node (ref "COB_LEFT2") (pin "14") (pintype "input"))
      (node (ref "COB_LEFT2") (pin "24") (pintype "input"))
      (node (ref "COB_LEFT2") (pin "25") (pintype "input"))
      (node (ref "COB_LEFT2") (pin "26") (pintype "input"))
      (node (ref "COB_LEFT2") (pin "3") (pintype "input"))
      (node (ref "COB_RIGHT1") (pin "1") (pintype "input"))
      (node (ref "COB_RIGHT1") (pin "15") (pintype "input"))
      (node (ref "COB_RIGHT1") (pin "21") (pintype "input"))
      (node (ref "COB_RIGHT1") (pin "4") (pintype "input"))
      (node (ref "COB_RIGHT1") (pin "7") (pintype "input"))
      (node (ref "COB_RIGHT2") (pin "1") (pintype "input"))
      (node (ref "COB_RIGHT2") (pin "15") (pintype "input"))
      (node (ref "COB_RIGHT2") (pin "24") (pintype "input"))
      (node (ref "COB_RIGHT2") (pin "7") (pintype "input"))
      (node (ref "COB_TOP1") (pin "13") (pintype "input"))
      (node (ref "COB_TOP1") (pin "23") (pintype "input"))
      (node (ref "COB_TOP1") (pin "24") (pintype "input"))
      (node (ref "COB_TOP1") (pin "4") (pintype "input"))
      (node (ref "COB_TOP2") (pin "29") (pintype "input"))
      (node (ref "COB_TOP2") (pin "3") (pintype "input"))
      (node (ref "COB_TOP2") (pin "30") (pintype "input"))
      (node (ref "COB_TOP2") (pin "4") (pintype "input"))
    )
    (net (code "189") (name "V5V") (class "Default")
      (node (ref "C10") (pin "1") (pinfunction "1_1") (pintype "passive"))
      (node (ref "C3") (pin "1") (pinfunction "1_1") (pintype "passive"))
      (node (ref "C4") (pin "1") (pinfunction "1_1") (pintype "passive"))
      (node (ref "C9") (pin "1") (pinfunction "1_1") (pintype "passive"))
      (node (ref "COB_LEFT1") (pin "32") (pintype "input"))
      (node (ref "COB_RIGHT2") (pin "18") (pintype "input"))
    )
    (net (code "190") (name "VDD") (class "Default")
      (node (ref "C1") (pin "1") (pinfunction "1_1") (pintype "passive"))
      (node (ref "C11") (pin "1") (pinfunction "1_1") (pintype "passive"))
      (node (ref "C12") (pin "1") (pinfunction "1_1") (pintype "passive"))
      (node (ref "C13") (pin "1") (pinfunction "1_1") (pintype "passive"))
      (node (ref "C14") (pin "1") (pinfunction "1_1") (pintype "passive"))
      (node (ref "C15") (pin "1") (pinfunction "1_1") (pintype "passive"))
      (node (ref "C16") (pin "1") (pinfunction "1_1") (pintype "passive"))
      (node (ref "C17") (pin "1") (pinfunction "1_1") (pintype "passive"))
      (node (ref "C18") (pin "1") (pinfunction "1_1") (pintype "passive"))
      (node (ref "C19") (pin "1") (pinfunction "1_1") (pintype "passive"))
      (node (ref "C2") (pin "1") (pinfunction "1_1") (pintype "passive"))
      (node (ref "C20") (pin "1") (pinfunction "1_1") (pintype "passive"))
      (node (ref "C21") (pin "1") (pinfunction "1_1") (pintype "passive"))
      (node (ref "C22") (pin "1") (pinfunction "1_1") (pintype "passive"))
      (node (ref "C23") (pin "1") (pinfunction "1_1") (pintype "passive"))
      (node (ref "C24") (pin "1") (pinfunction "1_1") (pintype "passive"))
      (node (ref "C25") (pin "1") (pinfunction "1_1") (pintype "passive"))
      (node (ref "C26") (pin "1") (pinfunction "1_1") (pintype "passive"))
      (node (ref "C27") (pin "1") (pinfunction "1_1") (pintype "passive"))
      (node (ref "C28") (pin "1") (pinfunction "1_1") (pintype "passive"))
      (node (ref "C29") (pin "1") (pinfunction "1_1") (pintype "passive"))
      (node (ref "C30") (pin "1") (pinfunction "1_1") (pintype "passive"))
      (node (ref "C31") (pin "1") (pinfunction "1_1") (pintype "passive"))
      (node (ref "C32") (pin "1") (pinfunction "1_1") (pintype "passive"))
      (node (ref "C33") (pin "1") (pinfunction "1_1") (pintype "passive"))
      (node (ref "C34") (pin "1") (pinfunction "1_1") (pintype "passive"))
      (node (ref "C5") (pin "1") (pinfunction "1_1") (pintype "passive"))
      (node (ref "C6") (pin "1") (pinfunction "1_1") (pintype "passive"))
      (node (ref "C7") (pin "1") (pinfunction "1_1") (pintype "passive"))
      (node (ref "C8") (pin "1") (pinfunction "1_1") (pintype "passive"))
      (node (ref "COB_BOTTOM2") (pin "2") (pintype "input"))
      (node (ref "COB_LEFT1") (pin "18") (pintype "input"))
      (node (ref "COB_LEFT1") (pin "20") (pintype "input"))
      (node (ref "COB_LEFT1") (pin "4") (pintype "input"))
      (node (ref "COB_LEFT2") (pin "2") (pintype "input"))
      (node (ref "COB_LEFT2") (pin "22") (pintype "input"))
      (node (ref "COB_LEFT2") (pin "27") (pintype "input"))
      (node (ref "COB_LEFT2") (pin "4") (pintype "input"))
      (node (ref "COB_RIGHT1") (pin "22") (pintype "input"))
      (node (ref "COB_RIGHT1") (pin "3") (pintype "input"))
      (node (ref "COB_RIGHT2") (pin "16") (pintype "input"))
      (node (ref "COB_RIGHT2") (pin "17") (pintype "input"))
      (node (ref "COB_RIGHT2") (pin "4") (pintype "input"))
      (node (ref "COB_RIGHT2") (pin "6") (pintype "input"))
      (node (ref "COB_TOP2") (pin "2") (pintype "input"))
    )
    (net (code "191") (name "VREAD") (class "Default")
      (node (ref "C43") (pin "1") (pinfunction "1_1") (pintype "passive"))
      (node (ref "C44") (pin "1") (pinfunction "1_1") (pintype "passive"))
      (node (ref "C47") (pin "1") (pinfunction "1_1") (pintype "passive"))
      (node (ref "C48") (pin "1") (pinfunction "1_1") (pintype "passive"))
      (node (ref "COB_LEFT1") (pin "30") (pintype "input"))
      (node (ref "COB_RIGHT2") (pin "21") (pintype "input"))
    )
    (net (code "192") (name "VSEL_BL_0") (class "Default")
      (node (ref "C49") (pin "1") (pinfunction "1_1") (pintype "passive"))
      (node (ref "C50") (pin "1") (pinfunction "1_1") (pintype "passive"))
      (node (ref "C57") (pin "1") (pinfunction "1_1") (pintype "passive"))
      (node (ref "C58") (pin "1") (pinfunction "1_1") (pintype "passive"))
      (node (ref "COB_LEFT1") (pin "27") (pintype "input"))
      (node (ref "COB_RIGHT2") (pin "22") (pintype "input"))
    )
    (net (code "193") (name "VSEL_BL_1") (class "Default")
      (node (ref "C51") (pin "1") (pinfunction "1_1") (pintype "passive"))
      (node (ref "C52") (pin "1") (pinfunction "1_1") (pintype "passive"))
      (node (ref "C61") (pin "1") (pinfunction "1_1") (pintype "passive"))
      (node (ref "C62") (pin "1") (pinfunction "1_1") (pintype "passive"))
      (node (ref "COB_LEFT1") (pin "25") (pintype "input"))
      (node (ref "COB_RIGHT2") (pin "29") (pintype "input"))
    )
    (net (code "194") (name "VSEL_SL_0") (class "Default")
      (node (ref "C35") (pin "1") (pinfunction "1_1") (pintype "passive"))
      (node (ref "C36") (pin "1") (pinfunction "1_1") (pintype "passive"))
      (node (ref "C37") (pin "1") (pinfunction "1_1") (pintype "passive"))
      (node (ref "C38") (pin "1") (pinfunction "1_1") (pintype "passive"))
      (node (ref "COB_LEFT1") (pin "26") (pintype "input"))
      (node (ref "COB_RIGHT2") (pin "25") (pintype "input"))
    )
    (net (code "195") (name "VSEL_SL_1") (class "Default")
      (node (ref "C45") (pin "1") (pinfunction "1_1") (pintype "passive"))
      (node (ref "C46") (pin "1") (pinfunction "1_1") (pintype "passive"))
      (node (ref "C55") (pin "1") (pinfunction "1_1") (pintype "passive"))
      (node (ref "C56") (pin "1") (pinfunction "1_1") (pintype "passive"))
      (node (ref "COB_LEFT1") (pin "23") (pintype "input"))
      (node (ref "COB_RIGHT2") (pin "23") (pintype "input"))
    )
    (net (code "196") (name "VSEL_WL") (class "Default")
      (node (ref "C53") (pin "1") (pinfunction "1_1") (pintype "passive"))
      (node (ref "C54") (pin "1") (pinfunction "1_1") (pintype "passive"))
      (node (ref "C59") (pin "1") (pinfunction "1_1") (pintype "passive"))
      (node (ref "C60") (pin "1") (pinfunction "1_1") (pintype "passive"))
      (node (ref "COB_LEFT1") (pin "29") (pintype "input"))
      (node (ref "COB_RIGHT2") (pin "20") (pintype "input"))
    )
    (net (code "197") (name "VUNSEL_WL") (class "Default")
      (node (ref "C39") (pin "1") (pinfunction "1_1") (pintype "passive"))
      (node (ref "C40") (pin "1") (pinfunction "1_1") (pintype "passive"))
      (node (ref "C41") (pin "1") (pinfunction "1_1") (pintype "passive"))
      (node (ref "C42") (pin "1") (pinfunction "1_1") (pintype "passive"))
      (node (ref "COB_LEFT1") (pin "28") (pintype "input"))
      (node (ref "COB_RIGHT2") (pin "19") (pintype "input"))
    )
    (net (code "198") (name "unconnected-(COB_RIGHT1-Pad5)") (class "Default")
      (node (ref "COB_RIGHT1") (pin "5") (pintype "input"))
    )
    (net (code "199") (name "unconnected-(COB_RIGHT1-Pad6)") (class "Default")
      (node (ref "COB_RIGHT1") (pin "6") (pintype "input"))
    )
    (net (code "200") (name "unconnected-(COB_RIGHT1-Pad8)") (class "Default")
      (node (ref "COB_RIGHT1") (pin "8") (pintype "input"))
    )
    (net (code "201") (name "unconnected-(COB_RIGHT1-Pad9)") (class "Default")
      (node (ref "COB_RIGHT1") (pin "9") (pintype "input"))
    )
    (net (code "202") (name "unconnected-(COB_RIGHT1-Pad10)") (class "Default")
      (node (ref "COB_RIGHT1") (pin "10") (pintype "input"))
    )
    (net (code "203") (name "unconnected-(COB_RIGHT1-Pad11)") (class "Default")
      (node (ref "COB_RIGHT1") (pin "11") (pintype "input"))
    )
    (net (code "204") (name "unconnected-(COB_RIGHT1-Pad12)") (class "Default")
      (node (ref "COB_RIGHT1") (pin "12") (pintype "input"))
    )
    (net (code "205") (name "unconnected-(COB_RIGHT1-Pad13)") (class "Default")
      (node (ref "COB_RIGHT1") (pin "13") (pintype "input"))
    )
    (net (code "206") (name "unconnected-(COB_RIGHT1-Pad14)") (class "Default")
      (node (ref "COB_RIGHT1") (pin "14") (pintype "input"))
    )
    (net (code "207") (name "unconnected-(COB_RIGHT1-Pad16)") (class "Default")
      (node (ref "COB_RIGHT1") (pin "16") (pintype "input"))
    )
    (net (code "208") (name "unconnected-(COB_RIGHT1-Pad18)") (class "Default")
      (node (ref "COB_RIGHT1") (pin "18") (pintype "input"))
    )
  )
)
